# RF_module.net
KiCad netlist of a schematic drawn in EAGLE
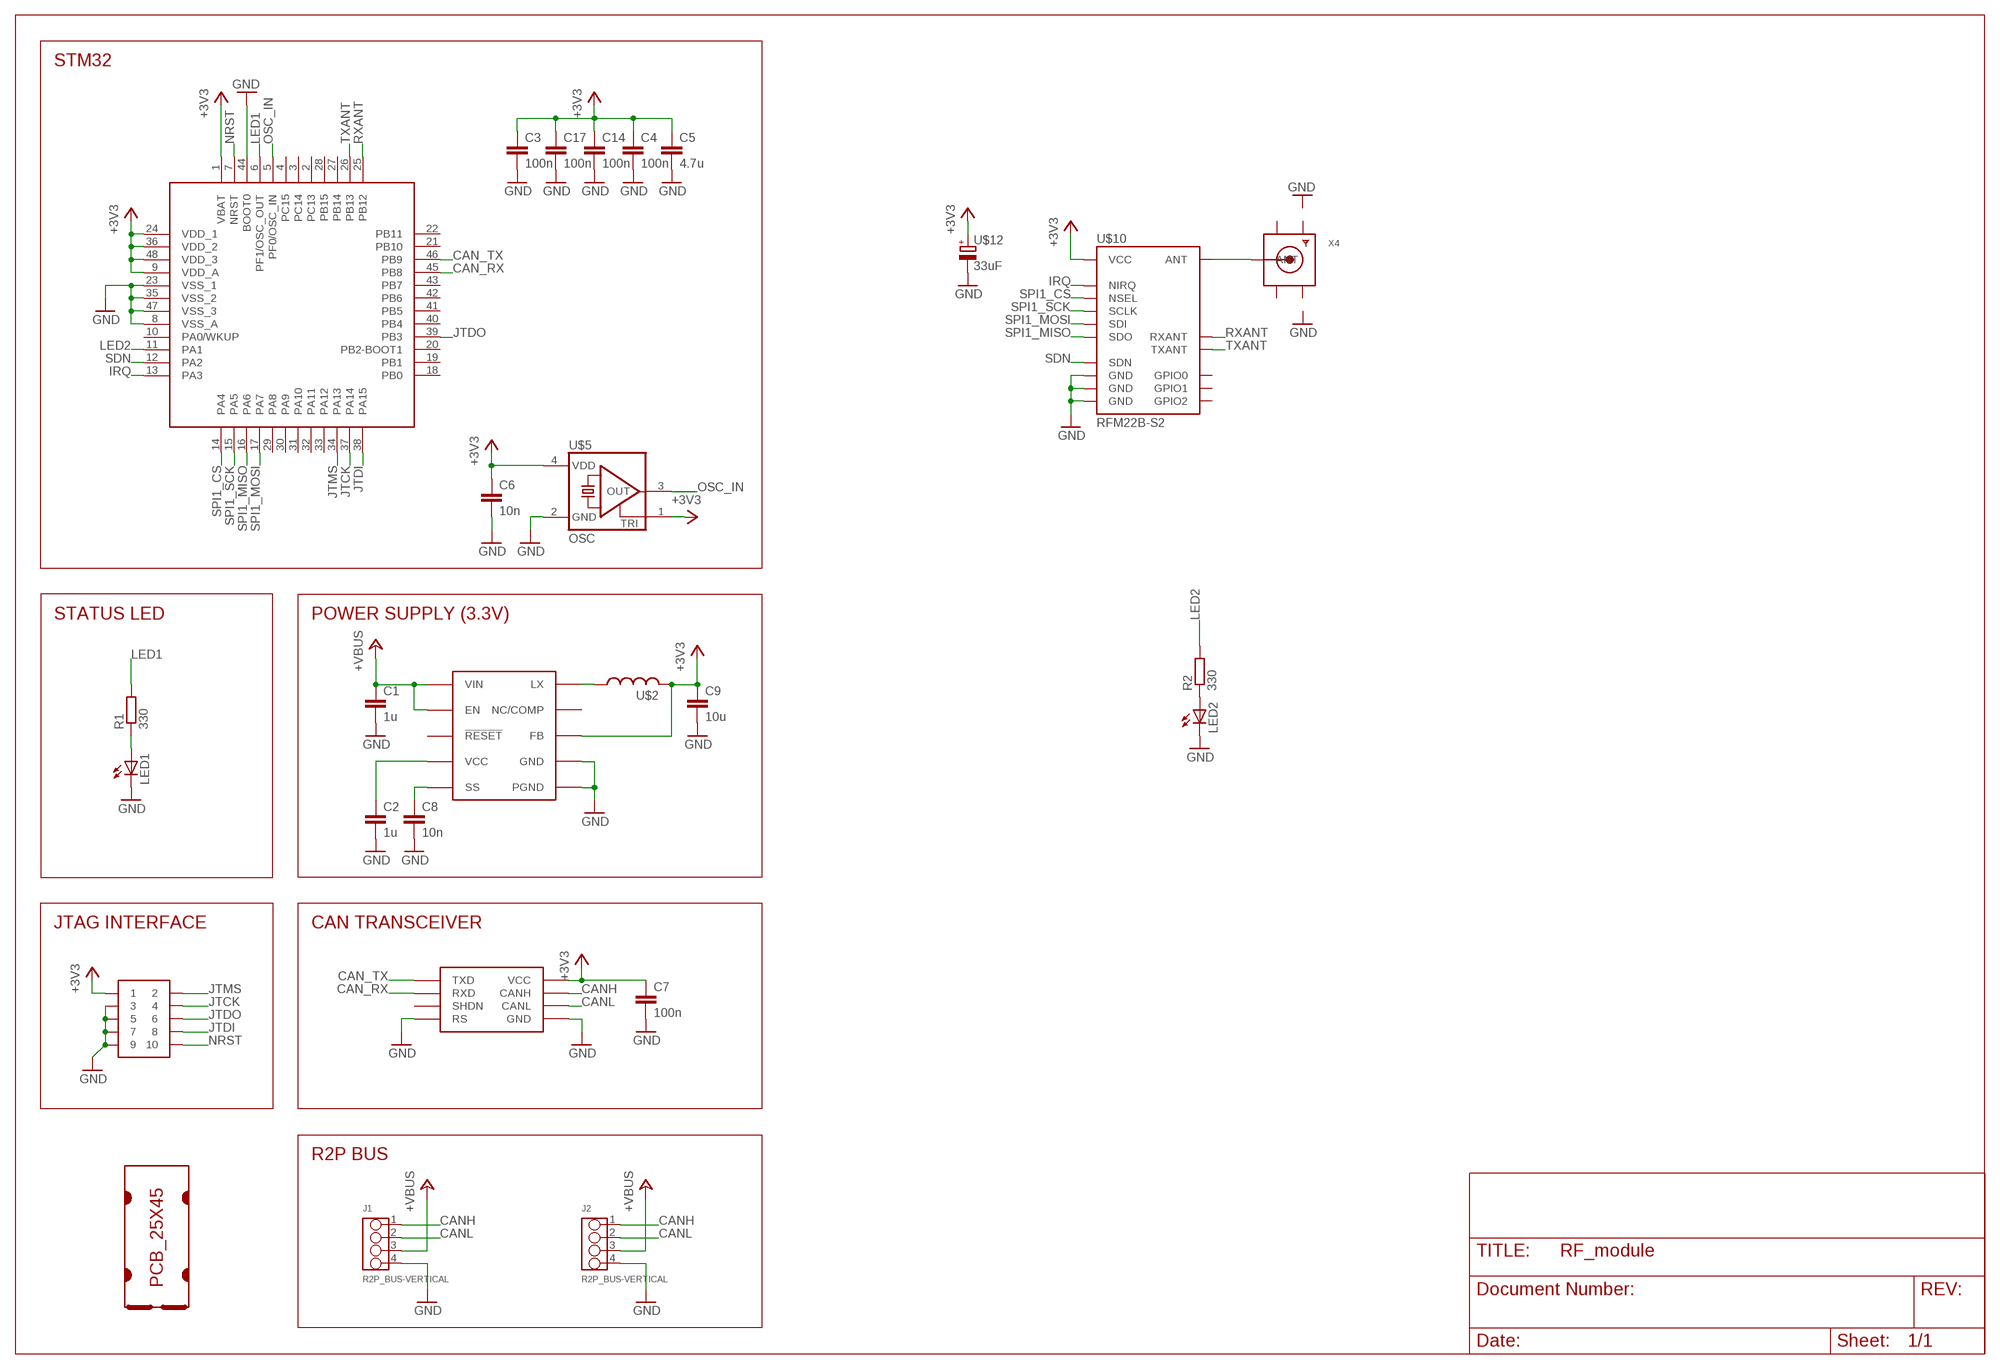
[diagram p0: schematic, sheet 1]

(export (version "E")
  (design (tool "Eeschema 10.0.6"))
  (components
    (comp (ref "C1")
      (value "1u")
      (footprint "eagle-import:C1206")
      (libsource (lib "eagle-import") (part "C1206"))
    )
    (comp (ref "C2")
      (value "1u")
      (footprint "eagle-import:C0603")
      (libsource (lib "eagle-import") (part "C0603"))
    )
    (comp (ref "C3")
      (value "100n")
      (footprint "eagle-import:C0603")
      (libsource (lib "eagle-import") (part "C0603"))
    )
    (comp (ref "C4")
      (value "100n")
      (footprint "eagle-import:C0603")
      (libsource (lib "eagle-import") (part "C0603"))
    )
    (comp (ref "C5")
      (value "4.7u")
      (footprint "eagle-import:C0805")
      (libsource (lib "eagle-import") (part "C0805"))
    )
    (comp (ref "C6")
      (value "10n")
      (footprint "eagle-import:C0603")
      (libsource (lib "eagle-import") (part "C0603"))
    )
    (comp (ref "C7")
      (value "100n")
      (footprint "eagle-import:C0603")
      (libsource (lib "eagle-import") (part "C0603"))
    )
    (comp (ref "C8")
      (value "10n")
      (footprint "eagle-import:C0603")
      (libsource (lib "eagle-import") (part "C0603"))
    )
    (comp (ref "C9")
      (value "10u")
      (footprint "eagle-import:C0805")
      (libsource (lib "eagle-import") (part "C0805"))
    )
    (comp (ref "C14")
      (value "100n")
      (footprint "eagle-import:C0603")
      (libsource (lib "eagle-import") (part "C0603"))
    )
    (comp (ref "C17")
      (value "100n")
      (footprint "eagle-import:C0603")
      (libsource (lib "eagle-import") (part "C0603"))
    )
    (comp (ref "J1")
      (value "R2P_BUS-VERTICAL")
      (footprint "eagle-import:OPL-EAGLE-LIBRARY_4P-2.0")
      (libsource (lib "eagle-import") (part "R2P_BUS-VERTICAL"))
    )
    (comp (ref "J2")
      (value "R2P_BUS-VERTICAL")
      (footprint "eagle-import:OPL-EAGLE-LIBRARY_4P-2.0")
      (libsource (lib "eagle-import") (part "R2P_BUS-VERTICAL"))
    )
    (comp (ref "LED1")
      (value "LED0805")
      (footprint "eagle-import:CHIPLED_0805")
      (libsource (lib "eagle-import") (part "LED0805"))
    )
    (comp (ref "LED2")
      (value "LED0805")
      (footprint "eagle-import:CHIPLED_0805")
      (libsource (lib "eagle-import") (part "LED0805"))
    )
    (comp (ref "R1")
      (value "330")
      (footprint "eagle-import:R0603")
      (libsource (lib "eagle-import") (part "R0603"))
    )
    (comp (ref "R2")
      (value "330")
      (footprint "eagle-import:R0603")
      (libsource (lib "eagle-import") (part "R0603"))
    )
    (comp (ref "SOT1")
      (value "MAX3051EKA")
      (footprint "eagle-import:SOT23-8L")
      (libsource (lib "eagle-import") (part "MAX3051EKA"))
    )
    (comp (ref "U$1")
      (value "PCB_25X45")
      (footprint "eagle-import:25X45")
      (libsource (lib "eagle-import") (part "PCB_25X45"))
    )
    (comp (ref "U$2")
      (value "LPS4018")
      (footprint "eagle-import:COILCRAFT_LPS4018")
      (libsource (lib "eagle-import") (part "LPS4018"))
    )
    (comp (ref "U$3")
      (value "MAX17501")
      (footprint "eagle-import:TDFN-10")
      (libsource (lib "eagle-import") (part "MAX17501"))
    )
    (comp (ref "U$4")
      (value "JTAG-TH")
      (footprint "eagle-import:SAMTEC_FTSH-105-TH")
      (libsource (lib "eagle-import") (part "JTAG-TH"))
    )
    (comp (ref "U$5")
      (value "OSC")
      (footprint "eagle-import:XTAL_2.5X2")
      (libsource (lib "eagle-import") (part "OSC"))
    )
    (comp (ref "U$6")
      (value "STM32F303CTX")
      (footprint "eagle-import:LQFP48")
      (libsource (lib "eagle-import") (part "STM32F303CTX"))
    )
    (comp (ref "U$10")
      (value "RFM22B-S2")
      (footprint "eagle-import:RFM22B-S2")
      (libsource (lib "eagle-import") (part "RFM22B-S2"))
    )
    (comp (ref "U$12")
      (value "33uF")
      (footprint "eagle-import:CPOL_B")
      (libsource (lib "eagle-import") (part "CPOL"))
    )
    (comp (ref "X4")
      (value "SMACONNECTOR_EDGE_UFL")
      (footprint "eagle-import:SMA_EDGELAUNCH_UFL")
      (libsource (lib "eagle-import") (part "SMACONNECTOR_EDGE_UFL"))
    )
  )
  (nets
    (net (code "1") (name "+3V3") (class "Default")
      (node (ref "C14") (pin "1") (pinfunction "1_1") (pintype "passive"))
      (node (ref "C17") (pin "1") (pinfunction "1_1") (pintype "passive"))
      (node (ref "C3") (pin "1") (pinfunction "1_1") (pintype "passive"))
      (node (ref "C4") (pin "1") (pinfunction "1_1") (pintype "passive"))
      (node (ref "C5") (pin "1") (pinfunction "1_1") (pintype "passive"))
      (node (ref "C6") (pin "1") (pinfunction "1_1") (pintype "passive"))
      (node (ref "C7") (pin "1") (pinfunction "1_1") (pintype "passive"))
      (node (ref "C9") (pin "1") (pinfunction "1_1") (pintype "passive"))
      (node (ref "SOT1") (pin "3") (pinfunction "VCC_3") (pintype "bidirectional"))
      (node (ref "U$10") (pin "P$5") (pinfunction "VCC_P$5") (pintype "bidirectional"))
      (node (ref "U$12") (pin "+") (pinfunction "+_+") (pintype "passive"))
      (node (ref "U$2") (pin "P$2") (pinfunction "2_P$2") (pintype "passive"))
      (node (ref "U$3") (pin "P$5") (pinfunction "FB_P$5") (pintype "bidirectional"))
      (node (ref "U$4") (pin "1") (pinfunction "1_1") (pintype "bidirectional"))
      (node (ref "U$5") (pin "1") (pinfunction "TRI_1") (pintype "input"))
      (node (ref "U$5") (pin "4") (pinfunction "VDD_4") (pintype "power_in"))
      (node (ref "U$6") (pin "1") (pinfunction "VBAT_1") (pintype "bidirectional"))
      (node (ref "U$6") (pin "24") (pinfunction "VDD_1_24") (pintype "bidirectional"))
      (node (ref "U$6") (pin "36") (pinfunction "VDD_2_36") (pintype "bidirectional"))
      (node (ref "U$6") (pin "48") (pinfunction "VDD_3_48") (pintype "bidirectional"))
      (node (ref "U$6") (pin "9") (pinfunction "VDD_A_9") (pintype "bidirectional"))
    )
    (net (code "2") (name "+VBUS") (class "Default")
      (node (ref "C1") (pin "1") (pinfunction "1_1") (pintype "passive"))
      (node (ref "J1") (pin "3") (pinfunction "3_3") (pintype "bidirectional"))
      (node (ref "J2") (pin "3") (pinfunction "3_3") (pintype "bidirectional"))
      (node (ref "U$3") (pin "P$2") (pinfunction "VIN_P$2") (pintype "bidirectional"))
      (node (ref "U$3") (pin "P$3") (pinfunction "EN_P$3") (pintype "bidirectional"))
    )
    (net (code "3") (name "/CANH") (class "Default")
      (node (ref "J1") (pin "1") (pinfunction "1_1") (pintype "bidirectional"))
      (node (ref "J2") (pin "1") (pinfunction "1_1") (pintype "bidirectional"))
      (node (ref "SOT1") (pin "7") (pinfunction "CANH_7") (pintype "bidirectional"))
    )
    (net (code "4") (name "/CANL") (class "Default")
      (node (ref "J1") (pin "2") (pinfunction "2_2") (pintype "bidirectional"))
      (node (ref "J2") (pin "2") (pinfunction "2_2") (pintype "bidirectional"))
      (node (ref "SOT1") (pin "6") (pinfunction "CANL_6") (pintype "bidirectional"))
    )
    (net (code "5") (name "/CAN_RX") (class "Default")
      (node (ref "SOT1") (pin "4") (pinfunction "RXD_4") (pintype "bidirectional"))
      (node (ref "U$6") (pin "45") (pinfunction "PB8_45") (pintype "bidirectional"))
    )
    (net (code "6") (name "/CAN_TX") (class "Default")
      (node (ref "SOT1") (pin "1") (pinfunction "TXD_1") (pintype "bidirectional"))
      (node (ref "U$6") (pin "46") (pinfunction "PB9_46") (pintype "bidirectional"))
    )
    (net (code "7") (name "/GND1") (class "Default")
      (node (ref "X4") (pin "GND@1") (pinfunction "GND1_GND@1") (pintype "power_in"))
    )
    (net (code "8") (name "/GND2") (class "Default")
      (node (ref "X4") (pin "GND@2") (pinfunction "GND2_GND@2") (pintype "power_in"))
    )
    (net (code "9") (name "/GND3") (class "Default")
      (node (ref "X4") (pin "GND@3") (pinfunction "GND3_GND@3") (pintype "power_in"))
    )
    (net (code "10") (name "/GND4") (class "Default")
      (node (ref "X4") (pin "GND@4") (pinfunction "GND4_GND@4") (pintype "power_in"))
    )
    (net (code "11") (name "/IRQ") (class "Default")
      (node (ref "U$10") (pin "P$14") (pinfunction "NIRQ_P$14") (pintype "output"))
      (node (ref "U$6") (pin "13") (pinfunction "PA3_13") (pintype "bidirectional"))
    )
    (net (code "12") (name "/JTCK") (class "Default")
      (node (ref "U$4") (pin "4") (pinfunction "4_4") (pintype "bidirectional"))
      (node (ref "U$6") (pin "37") (pinfunction "PA14_37") (pintype "bidirectional"))
    )
    (net (code "13") (name "/JTDI") (class "Default")
      (node (ref "U$4") (pin "8") (pinfunction "8_8") (pintype "bidirectional"))
      (node (ref "U$6") (pin "38") (pinfunction "PA15_38") (pintype "bidirectional"))
    )
    (net (code "14") (name "/JTDO") (class "Default")
      (node (ref "U$4") (pin "6") (pinfunction "6_6") (pintype "bidirectional"))
      (node (ref "U$6") (pin "39") (pinfunction "PB3_39") (pintype "bidirectional"))
    )
    (net (code "15") (name "/JTMS") (class "Default")
      (node (ref "U$4") (pin "2") (pinfunction "2_2") (pintype "bidirectional"))
      (node (ref "U$6") (pin "34") (pinfunction "PA13_34") (pintype "bidirectional"))
    )
    (net (code "16") (name "/LED1") (class "Default")
      (node (ref "R1") (pin "2") (pinfunction "2_2") (pintype "passive"))
      (node (ref "U$6") (pin "6") (pinfunction "PF1/OSC_OUT_6") (pintype "bidirectional"))
    )
    (net (code "17") (name "/LED2") (class "Default")
      (node (ref "R2") (pin "2") (pinfunction "2_2") (pintype "passive"))
      (node (ref "U$6") (pin "11") (pinfunction "PA1_11") (pintype "bidirectional"))
    )
    (net (code "18") (name "/NRST") (class "Default")
      (node (ref "U$4") (pin "10") (pinfunction "10_10") (pintype "bidirectional"))
      (node (ref "U$6") (pin "7") (pinfunction "NRST_7") (pintype "bidirectional"))
    )
    (net (code "19") (name "/OSC_IN") (class "Default")
      (node (ref "U$5") (pin "3") (pinfunction "OUT_3") (pintype "output"))
      (node (ref "U$6") (pin "5") (pinfunction "PF0/OSC_IN_5") (pintype "bidirectional"))
    )
    (net (code "20") (name "/RXANT") (class "Default")
      (node (ref "U$10") (pin "P$3") (pinfunction "RXANT_P$3") (pintype "input"))
      (node (ref "U$6") (pin "25") (pinfunction "PB12_25") (pintype "bidirectional"))
    )
    (net (code "21") (name "/SDN") (class "Default")
      (node (ref "U$10") (pin "P$15") (pinfunction "SDN_P$15") (pintype "input"))
      (node (ref "U$6") (pin "12") (pinfunction "PA2_12") (pintype "bidirectional"))
    )
    (net (code "22") (name "/SPI1_CS") (class "Default")
      (node (ref "U$10") (pin "P$13") (pinfunction "NSEL_P$13") (pintype "input"))
      (node (ref "U$6") (pin "14") (pinfunction "PA4_14") (pintype "bidirectional"))
    )
    (net (code "23") (name "/SPI1_MISO") (class "Default")
      (node (ref "U$10") (pin "P$10") (pinfunction "SDO_P$10") (pintype "output"))
      (node (ref "U$6") (pin "16") (pinfunction "PA6_16") (pintype "bidirectional"))
    )
    (net (code "24") (name "/SPI1_MOSI") (class "Default")
      (node (ref "U$10") (pin "P$11") (pinfunction "SDI_P$11") (pintype "input"))
      (node (ref "U$6") (pin "17") (pinfunction "PA7_17") (pintype "bidirectional"))
    )
    (net (code "25") (name "/SPI1_SCK") (class "Default")
      (node (ref "U$10") (pin "P$12") (pinfunction "SCLK_P$12") (pintype "input"))
      (node (ref "U$6") (pin "15") (pinfunction "PA5_15") (pintype "bidirectional"))
    )
    (net (code "26") (name "/TXANT") (class "Default")
      (node (ref "U$10") (pin "P$4") (pinfunction "TXANT_P$4") (pintype "input"))
      (node (ref "U$6") (pin "26") (pinfunction "PB13_26") (pintype "bidirectional"))
    )
    (net (code "27") (name "GND") (class "Default")
      (node (ref "C1") (pin "2") (pinfunction "2_2") (pintype "passive"))
      (node (ref "C14") (pin "2") (pinfunction "2_2") (pintype "passive"))
      (node (ref "C17") (pin "2") (pinfunction "2_2") (pintype "passive"))
      (node (ref "C2") (pin "2") (pinfunction "2_2") (pintype "passive"))
      (node (ref "C3") (pin "2") (pinfunction "2_2") (pintype "passive"))
      (node (ref "C4") (pin "2") (pinfunction "2_2") (pintype "passive"))
      (node (ref "C5") (pin "2") (pinfunction "2_2") (pintype "passive"))
      (node (ref "C6") (pin "2") (pinfunction "2_2") (pintype "passive"))
      (node (ref "C7") (pin "2") (pinfunction "2_2") (pintype "passive"))
      (node (ref "C8") (pin "2") (pinfunction "2_2") (pintype "passive"))
      (node (ref "C9") (pin "2") (pinfunction "2_2") (pintype "passive"))
      (node (ref "J1") (pin "4") (pinfunction "4_4") (pintype "bidirectional"))
      (node (ref "J2") (pin "4") (pinfunction "4_4") (pintype "bidirectional"))
      (node (ref "LED1") (pin "C") (pinfunction "C_C") (pintype "passive"))
      (node (ref "LED2") (pin "C") (pinfunction "C_C") (pintype "passive"))
      (node (ref "SOT1") (pin "2") (pinfunction "GND_2") (pintype "bidirectional"))
      (node (ref "SOT1") (pin "8") (pinfunction "RS_8") (pintype "bidirectional"))
      (node (ref "U$10") (pin "P$16") (pinfunction "GND_P$16") (pintype "power_in"))
      (node (ref "U$10") (pin "P$2") (pinfunction "GND_P$2") (pintype "power_in"))
      (node (ref "U$10") (pin "P$9") (pinfunction "GND_P$9") (pintype "power_in"))
      (node (ref "U$12") (pin "-") (pinfunction "-_-") (pintype "passive"))
      (node (ref "U$3") (pin "P$1") (pinfunction "PGND_P$1") (pintype "bidirectional"))
      (node (ref "U$3") (pin "P$11") (pinfunction "PGND_P$11") (pintype "bidirectional"))
      (node (ref "U$3") (pin "P$9") (pinfunction "GND_P$9") (pintype "bidirectional"))
      (node (ref "U$4") (pin "3") (pinfunction "3_3") (pintype "bidirectional"))
      (node (ref "U$4") (pin "5") (pinfunction "5_5") (pintype "bidirectional"))
      (node (ref "U$4") (pin "7") (pinfunction "7_7") (pintype "bidirectional"))
      (node (ref "U$4") (pin "9") (pinfunction "9_9") (pintype "bidirectional"))
      (node (ref "U$5") (pin "2") (pinfunction "GND_2") (pintype "power_in"))
      (node (ref "U$6") (pin "23") (pinfunction "VSS_1_23") (pintype "bidirectional"))
      (node (ref "U$6") (pin "35") (pinfunction "VSS_2_35") (pintype "bidirectional"))
      (node (ref "U$6") (pin "44") (pinfunction "BOOT0_44") (pintype "bidirectional"))
      (node (ref "U$6") (pin "47") (pinfunction "VSS_3_47") (pintype "bidirectional"))
      (node (ref "U$6") (pin "8") (pinfunction "VSS_A_8") (pintype "bidirectional"))
    )
    (net (code "28") (name "Net-(LED1-PadA)") (class "Default")
      (node (ref "LED1") (pin "A") (pinfunction "A_A") (pintype "passive"))
      (node (ref "R1") (pin "1") (pinfunction "1_1") (pintype "passive"))
    )
    (net (code "29") (name "Net-(LED2-PadA)") (class "Default")
      (node (ref "LED2") (pin "A") (pinfunction "A_A") (pintype "passive"))
      (node (ref "R2") (pin "1") (pinfunction "1_1") (pintype "passive"))
    )
    (net (code "30") (name "Net-(U$2-1)") (class "Default")
      (node (ref "U$2") (pin "P$1") (pinfunction "1_P$1") (pintype "passive"))
      (node (ref "U$3") (pin "P$10") (pinfunction "LX_P$10") (pintype "bidirectional"))
    )
    (net (code "31") (name "Net-(U$3-SS)") (class "Default")
      (node (ref "C8") (pin "1") (pinfunction "1_1") (pintype "passive"))
      (node (ref "U$3") (pin "P$6") (pinfunction "SS_P$6") (pintype "bidirectional"))
    )
    (net (code "32") (name "Net-(U$3-VCC)") (class "Default")
      (node (ref "C2") (pin "1") (pinfunction "1_1") (pintype "passive"))
      (node (ref "U$3") (pin "P$4") (pinfunction "VCC_P$4") (pintype "bidirectional"))
    )
    (net (code "33") (name "Net-(U$10-ANT)") (class "Default")
      (node (ref "U$10") (pin "P$1") (pinfunction "ANT_P$1") (pintype "bidirectional"))
      (node (ref "X4") (pin "P") (pinfunction "ANT_P") (pintype "bidirectional"))
    )
    (net (code "34") (name "unconnected-(SOT1-SHDN-Pad5)") (class "Default")
      (node (ref "SOT1") (pin "5") (pinfunction "SHDN_5") (pintype "bidirectional"))
    )
    (net (code "35") (name "unconnected-(U$3-NC{slash}COMP-PadP$7)") (class "Default")
      (node (ref "U$3") (pin "P$7") (pinfunction "NC/COMP_P$7") (pintype "bidirectional"))
    )
    (net (code "36") (name "unconnected-(U$3-~{RESET}-PadP$8)") (class "Default")
      (node (ref "U$3") (pin "P$8") (pinfunction "~{RESET}_P$8") (pintype "bidirectional"))
    )
    (net (code "37") (name "unconnected-(U$6-PA0{slash}WKUP-Pad10)") (class "Default")
      (node (ref "U$6") (pin "10") (pinfunction "PA0/WKUP_10") (pintype "bidirectional"))
    )
    (net (code "38") (name "unconnected-(U$6-PA8-Pad29)") (class "Default")
      (node (ref "U$6") (pin "29") (pinfunction "PA8_29") (pintype "bidirectional"))
    )
    (net (code "39") (name "unconnected-(U$6-PA9-Pad30)") (class "Default")
      (node (ref "U$6") (pin "30") (pinfunction "PA9_30") (pintype "bidirectional"))
    )
    (net (code "40") (name "unconnected-(U$6-PA10-Pad31)") (class "Default")
      (node (ref "U$6") (pin "31") (pinfunction "PA10_31") (pintype "bidirectional"))
    )
    (net (code "41") (name "unconnected-(U$6-PA11-Pad32)") (class "Default")
      (node (ref "U$6") (pin "32") (pinfunction "PA11_32") (pintype "bidirectional"))
    )
    (net (code "42") (name "unconnected-(U$6-PA12-Pad33)") (class "Default")
      (node (ref "U$6") (pin "33") (pinfunction "PA12_33") (pintype "bidirectional"))
    )
    (net (code "43") (name "unconnected-(U$6-PB0-Pad18)") (class "Default")
      (node (ref "U$6") (pin "18") (pinfunction "PB0_18") (pintype "bidirectional"))
    )
    (net (code "44") (name "unconnected-(U$6-PB1-Pad19)") (class "Default")
      (node (ref "U$6") (pin "19") (pinfunction "PB1_19") (pintype "bidirectional"))
    )
    (net (code "45") (name "unconnected-(U$6-PB2-BOOT1-Pad20)") (class "Default")
      (node (ref "U$6") (pin "20") (pinfunction "PB2-BOOT1_20") (pintype "bidirectional"))
    )
    (net (code "46") (name "unconnected-(U$6-PB4-Pad40)") (class "Default")
      (node (ref "U$6") (pin "40") (pinfunction "PB4_40") (pintype "bidirectional"))
    )
    (net (code "47") (name "unconnected-(U$6-PB5-Pad41)") (class "Default")
      (node (ref "U$6") (pin "41") (pinfunction "PB5_41") (pintype "bidirectional"))
    )
    (net (code "48") (name "unconnected-(U$6-PB6-Pad42)") (class "Default")
      (node (ref "U$6") (pin "42") (pinfunction "PB6_42") (pintype "bidirectional"))
    )
    (net (code "49") (name "unconnected-(U$6-PB7-Pad43)") (class "Default")
      (node (ref "U$6") (pin "43") (pinfunction "PB7_43") (pintype "bidirectional"))
    )
    (net (code "50") (name "unconnected-(U$6-PB10-Pad21)") (class "Default")
      (node (ref "U$6") (pin "21") (pinfunction "PB10_21") (pintype "bidirectional"))
    )
    (net (code "51") (name "unconnected-(U$6-PB11-Pad22)") (class "Default")
      (node (ref "U$6") (pin "22") (pinfunction "PB11_22") (pintype "bidirectional"))
    )
    (net (code "52") (name "unconnected-(U$6-PB14-Pad27)") (class "Default")
      (node (ref "U$6") (pin "27") (pinfunction "PB14_27") (pintype "bidirectional"))
    )
    (net (code "53") (name "unconnected-(U$6-PB15-Pad28)") (class "Default")
      (node (ref "U$6") (pin "28") (pinfunction "PB15_28") (pintype "bidirectional"))
    )
    (net (code "54") (name "unconnected-(U$6-PC13-Pad2)") (class "Default")
      (node (ref "U$6") (pin "2") (pinfunction "PC13_2") (pintype "bidirectional"))
    )
    (net (code "55") (name "unconnected-(U$6-PC14-Pad3)") (class "Default")
      (node (ref "U$6") (pin "3") (pinfunction "PC14_3") (pintype "bidirectional"))
    )
    (net (code "56") (name "unconnected-(U$6-PC15-Pad4)") (class "Default")
      (node (ref "U$6") (pin "4") (pinfunction "PC15_4") (pintype "bidirectional"))
    )
    (net (code "57") (name "unconnected-(U$10-GPIO0-PadP$6)") (class "Default")
      (node (ref "U$10") (pin "P$6") (pinfunction "GPIO0_P$6") (pintype "bidirectional"))
    )
    (net (code "58") (name "unconnected-(U$10-GPIO1-PadP$7)") (class "Default")
      (node (ref "U$10") (pin "P$7") (pinfunction "GPIO1_P$7") (pintype "bidirectional"))
    )
    (net (code "59") (name "unconnected-(U$10-GPIO2-PadP$8)") (class "Default")
      (node (ref "U$10") (pin "P$8") (pinfunction "GPIO2_P$8") (pintype "bidirectional"))
    )
  )
)
